# Pinscape_Pico_Expansion_Board_-_DIY_Frie.net
KiCad netlist of a schematic drawn in EAGLE
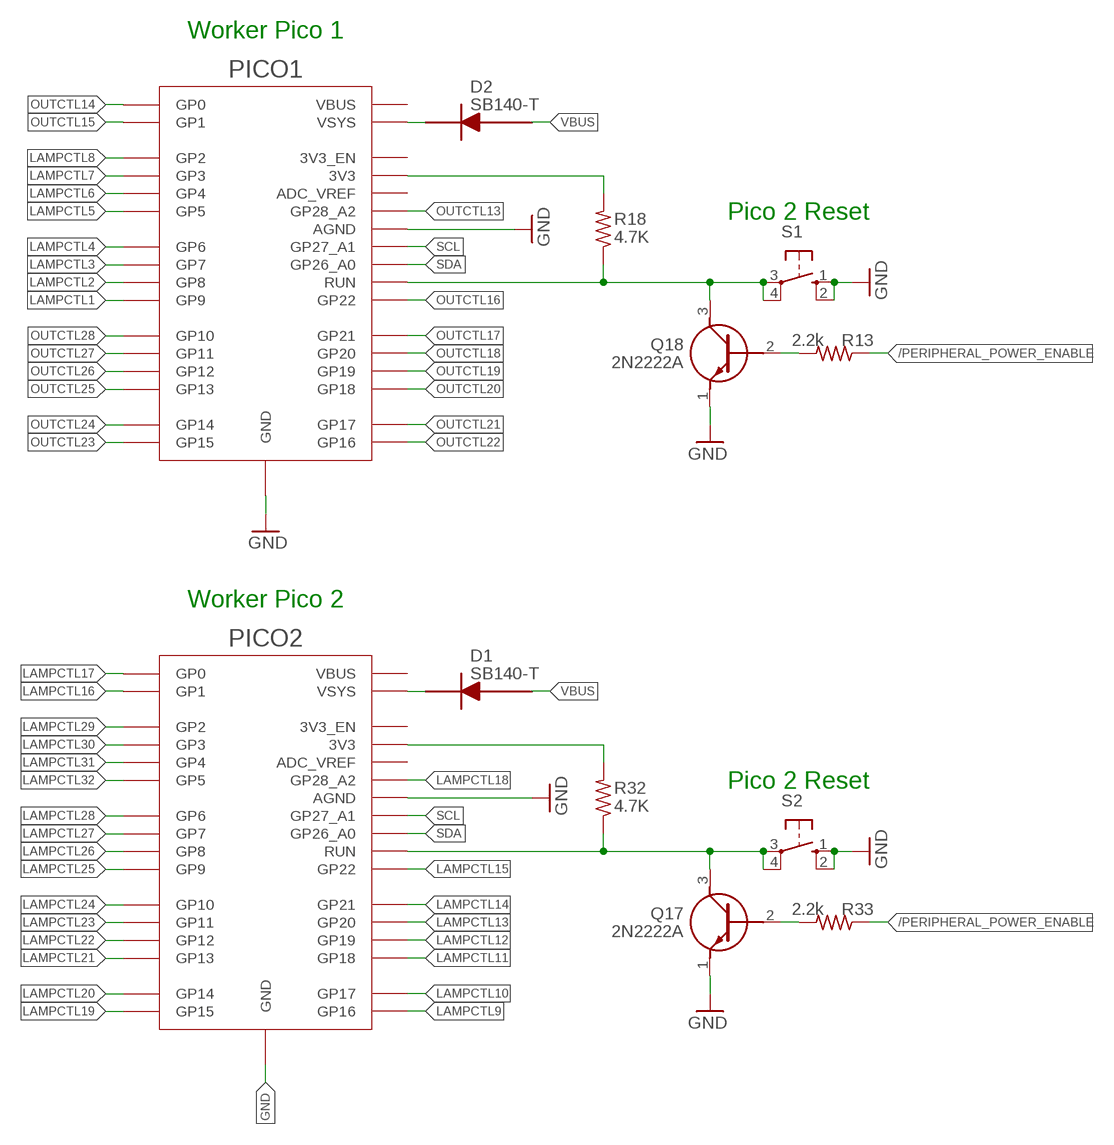
[diagram p0: schematic, sheet 1]
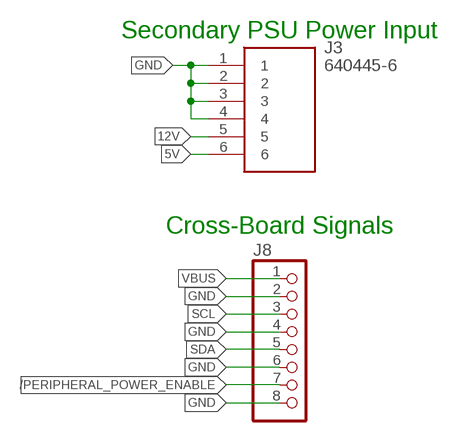
[diagram p1: schematic, sheet 2]
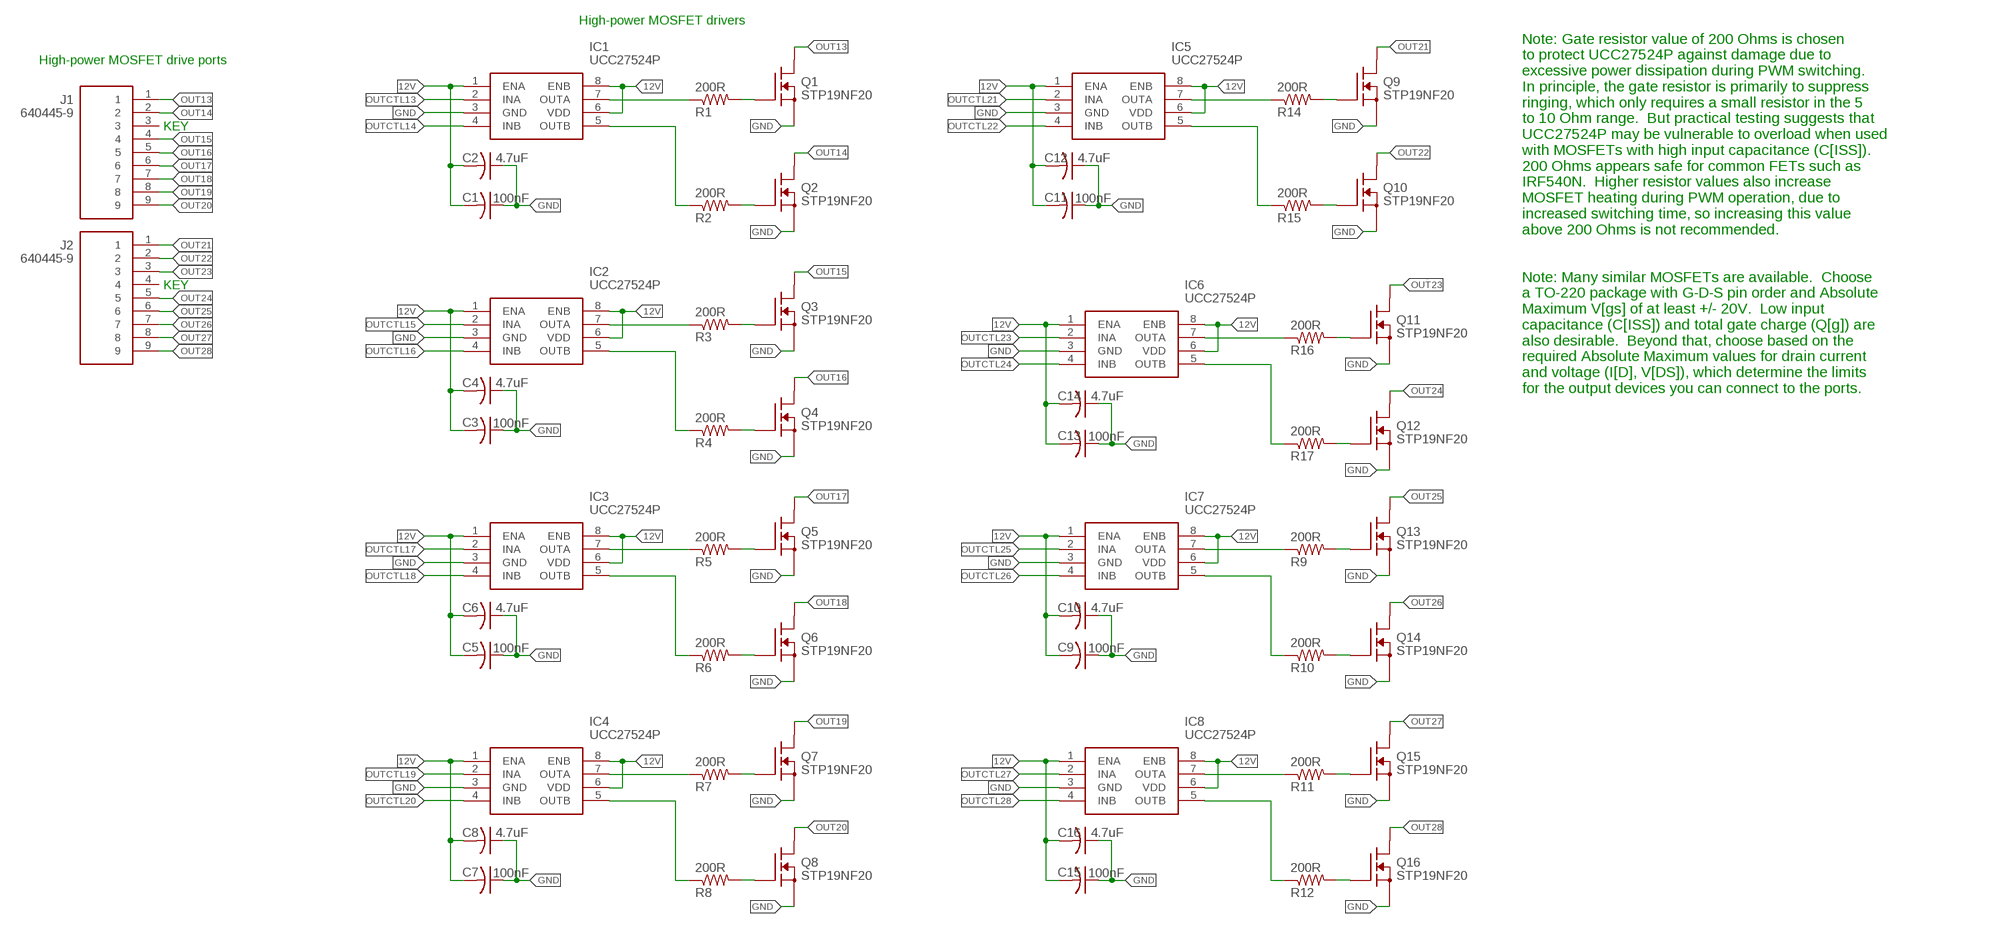
[diagram p2: schematic, sheet 3]
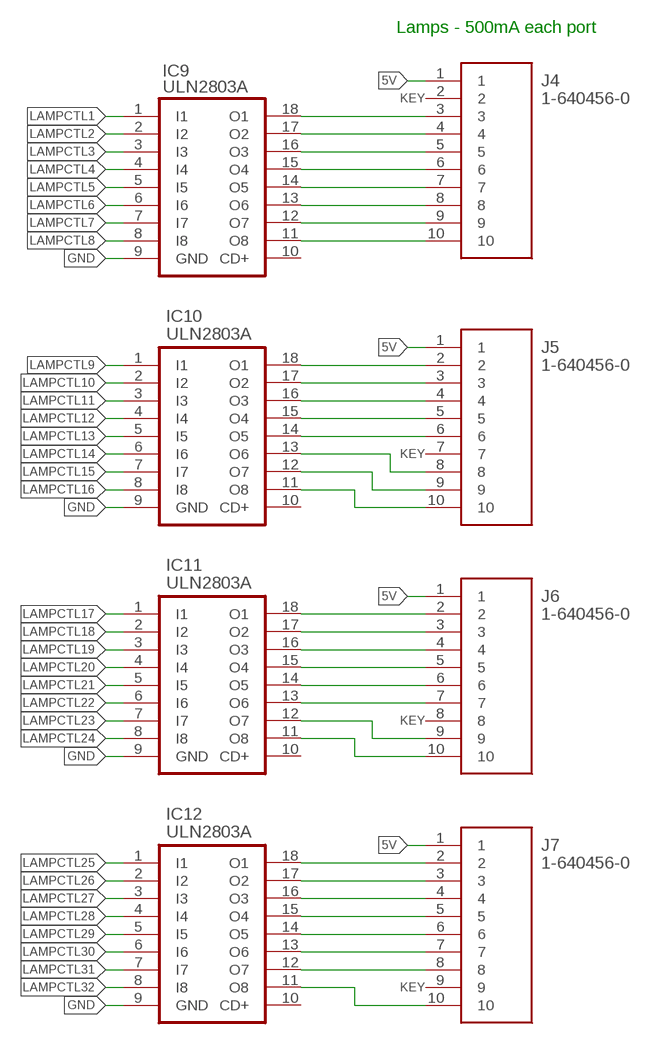
[diagram p3: schematic, sheet 4]
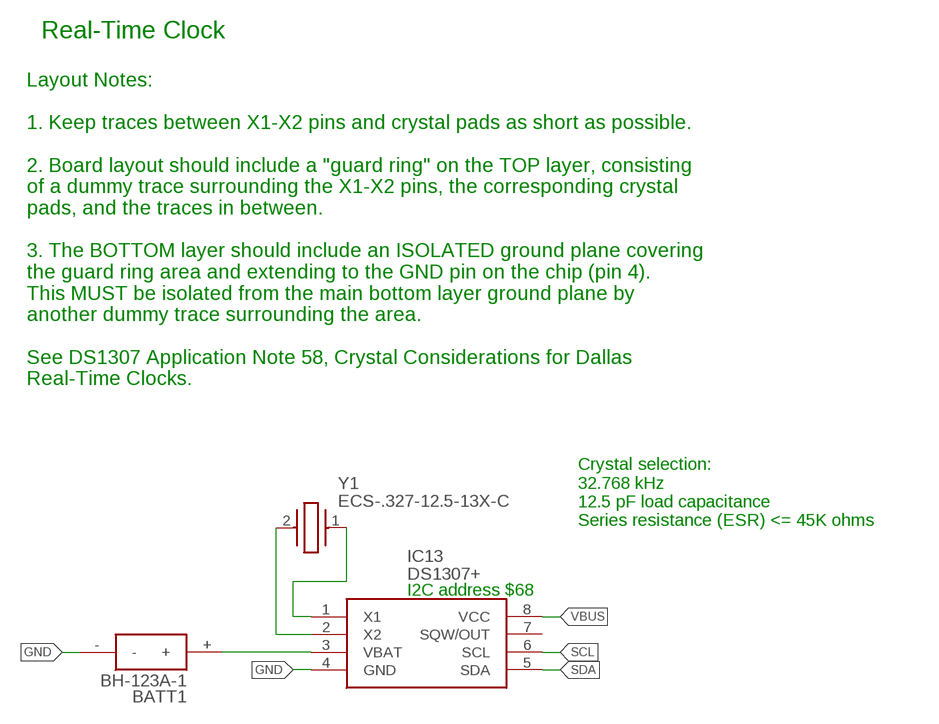
[diagram p4: schematic, sheet 5]
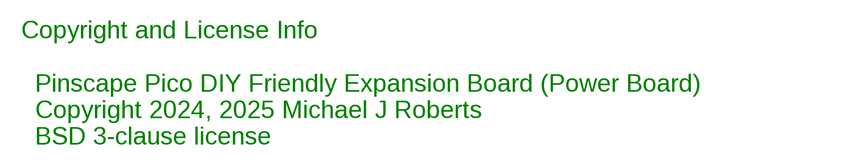
[diagram p5: schematic, sheet 6]

(export (version "E")
  (design (tool "Eeschema 10.0.6"))
  (components
    (comp (ref "C1")
      (value "100nF")
      (footprint "eagle-import:C025-024X044")
      (fields (field (name "PARTNO") "21RZ310-RC"))
      (libsource (lib "eagle-import") (part "C-US025-024X044"))
    )
    (comp (ref "C2")
      (value "4.7uF")
      (footprint "eagle-import:C025-024X044")
      (fields (field (name "PARTNO") "810-FG14X5R1H475KRT0"))
      (libsource (lib "eagle-import") (part "C-US025-024X044"))
    )
    (comp (ref "C3")
      (value "100nF")
      (footprint "eagle-import:C025-024X044")
      (fields (field (name "PARTNO") "21RZ310-RC"))
      (libsource (lib "eagle-import") (part "C-US025-024X044"))
    )
    (comp (ref "C4")
      (value "4.7uF")
      (footprint "eagle-import:C025-024X044")
      (fields (field (name "PARTNO") "810-FG14X5R1H475KRT0"))
      (libsource (lib "eagle-import") (part "C-US025-024X044"))
    )
    (comp (ref "C5")
      (value "100nF")
      (footprint "eagle-import:C025-024X044")
      (fields (field (name "PARTNO") "21RZ310-RC"))
      (libsource (lib "eagle-import") (part "C-US025-024X044"))
    )
    (comp (ref "C6")
      (value "4.7uF")
      (footprint "eagle-import:C025-024X044")
      (fields (field (name "PARTNO") "810-FG14X5R1H475KRT0"))
      (libsource (lib "eagle-import") (part "C-US025-024X044"))
    )
    (comp (ref "C7")
      (value "100nF")
      (footprint "eagle-import:C025-024X044")
      (fields (field (name "PARTNO") "21RZ310-RC"))
      (libsource (lib "eagle-import") (part "C-US025-024X044"))
    )
    (comp (ref "C8")
      (value "4.7uF")
      (footprint "eagle-import:C025-024X044")
      (fields (field (name "PARTNO") "810-FG14X5R1H475KRT0"))
      (libsource (lib "eagle-import") (part "C-US025-024X044"))
    )
    (comp (ref "C9")
      (value "100nF")
      (footprint "eagle-import:C025-024X044")
      (fields (field (name "PARTNO") "21RZ310-RC"))
      (libsource (lib "eagle-import") (part "C-US025-024X044"))
    )
    (comp (ref "C10")
      (value "4.7uF")
      (footprint "eagle-import:C025-024X044")
      (fields (field (name "PARTNO") "810-FG14X5R1H475KRT0"))
      (libsource (lib "eagle-import") (part "C-US025-024X044"))
    )
    (comp (ref "C11")
      (value "100nF")
      (footprint "eagle-import:C025-024X044")
      (fields (field (name "PARTNO") "21RZ310-RC"))
      (libsource (lib "eagle-import") (part "C-US025-024X044"))
    )
    (comp (ref "C12")
      (value "4.7uF")
      (footprint "eagle-import:C025-024X044")
      (fields (field (name "PARTNO") "810-FG14X5R1H475KRT0"))
      (libsource (lib "eagle-import") (part "C-US025-024X044"))
    )
    (comp (ref "C13")
      (value "100nF")
      (footprint "eagle-import:C025-024X044")
      (fields (field (name "PARTNO") "21RZ310-RC"))
      (libsource (lib "eagle-import") (part "C-US025-024X044"))
    )
    (comp (ref "C14")
      (value "4.7uF")
      (footprint "eagle-import:C025-024X044")
      (fields (field (name "PARTNO") "810-FG14X5R1H475KRT0"))
      (libsource (lib "eagle-import") (part "C-US025-024X044"))
    )
    (comp (ref "C15")
      (value "100nF")
      (footprint "eagle-import:C025-024X044")
      (fields (field (name "PARTNO") "21RZ310-RC"))
      (libsource (lib "eagle-import") (part "C-US025-024X044"))
    )
    (comp (ref "C16")
      (value "4.7uF")
      (footprint "eagle-import:C025-024X044")
      (fields (field (name "PARTNO") "810-FG14X5R1H475KRT0"))
      (libsource (lib "eagle-import") (part "C-US025-024X044"))
    )
    (comp (ref "IC1")
      (value "UCC27524P")
      (footprint "eagle-import:DIP794W53P254L959H508Q8N")
      (fields (field (name "MOUSER_PART_NUMBER") "595-UCC27524P"))
      (libsource (lib "eagle-import") (part "UCC27524P"))
    )
    (comp (ref "IC2")
      (value "UCC27524P")
      (footprint "eagle-import:DIP794W53P254L959H508Q8N")
      (fields (field (name "MOUSER_PART_NUMBER") "595-UCC27524P"))
      (libsource (lib "eagle-import") (part "UCC27524P"))
    )
    (comp (ref "IC3")
      (value "UCC27524P")
      (footprint "eagle-import:DIP794W53P254L959H508Q8N")
      (fields (field (name "MOUSER_PART_NUMBER") "595-UCC27524P"))
      (libsource (lib "eagle-import") (part "UCC27524P"))
    )
    (comp (ref "IC4")
      (value "UCC27524P")
      (footprint "eagle-import:DIP794W53P254L959H508Q8N")
      (fields (field (name "MOUSER_PART_NUMBER") "595-UCC27524P"))
      (libsource (lib "eagle-import") (part "UCC27524P"))
    )
    (comp (ref "IC5")
      (value "UCC27524P")
      (footprint "eagle-import:DIP794W53P254L959H508Q8N")
      (fields (field (name "MOUSER_PART_NUMBER") "595-UCC27524P"))
      (libsource (lib "eagle-import") (part "UCC27524P"))
    )
    (comp (ref "IC6")
      (value "UCC27524P")
      (footprint "eagle-import:DIP794W53P254L959H508Q8N")
      (fields (field (name "MOUSER_PART_NUMBER") "595-UCC27524P"))
      (libsource (lib "eagle-import") (part "UCC27524P"))
    )
    (comp (ref "IC7")
      (value "UCC27524P")
      (footprint "eagle-import:DIP794W53P254L959H508Q8N")
      (fields (field (name "MOUSER_PART_NUMBER") "595-UCC27524P"))
      (libsource (lib "eagle-import") (part "UCC27524P"))
    )
    (comp (ref "IC8")
      (value "UCC27524P")
      (footprint "eagle-import:DIP794W53P254L959H508Q8N")
      (fields (field (name "MOUSER_PART_NUMBER") "595-UCC27524P"))
      (libsource (lib "eagle-import") (part "UCC27524P"))
    )
    (comp (ref "J1")
      (value "640445-9")
      (footprint "eagle-import:SHDR9W117P0X396_1X9_3566X762X1")
      (fields (field (name "MOUSER_PART_NUMBER") "571-6404459"))
      (libsource (lib "eagle-import") (part "640445-9"))
    )
    (comp (ref "J2")
      (value "640445-9")
      (footprint "eagle-import:SHDR9W117P0X396_1X9_3566X762X1")
      (fields (field (name "MOUSER_PART_NUMBER") "571-6404459"))
      (libsource (lib "eagle-import") (part "640445-9"))
    )
    (comp (ref "Q1")
      (value "STP19NF20")
      (footprint "eagle-import:TO220BV")
      (fields (field (name "PARTNO") "FDPF085N10A"))
      (libsource (lib "eagle-import") (part "BUK7575-55A"))
    )
    (comp (ref "Q2")
      (value "STP19NF20")
      (footprint "eagle-import:TO220BV")
      (fields (field (name "PARTNO") "FDPF085N10A"))
      (libsource (lib "eagle-import") (part "BUK7575-55A"))
    )
    (comp (ref "Q3")
      (value "STP19NF20")
      (footprint "eagle-import:TO220BV")
      (fields (field (name "PARTNO") "FDPF085N10A"))
      (libsource (lib "eagle-import") (part "BUK7575-55A"))
    )
    (comp (ref "Q4")
      (value "STP19NF20")
      (footprint "eagle-import:TO220BV")
      (fields (field (name "PARTNO") "FDPF085N10A"))
      (libsource (lib "eagle-import") (part "BUK7575-55A"))
    )
    (comp (ref "Q5")
      (value "STP19NF20")
      (footprint "eagle-import:TO220BV")
      (fields (field (name "PARTNO") "FDPF085N10A"))
      (libsource (lib "eagle-import") (part "BUK7575-55A"))
    )
    (comp (ref "Q6")
      (value "STP19NF20")
      (footprint "eagle-import:TO220BV")
      (fields (field (name "PARTNO") "FDPF085N10A"))
      (libsource (lib "eagle-import") (part "BUK7575-55A"))
    )
    (comp (ref "Q7")
      (value "STP19NF20")
      (footprint "eagle-import:TO220BV")
      (fields (field (name "PARTNO") "FDPF085N10A"))
      (libsource (lib "eagle-import") (part "BUK7575-55A"))
    )
    (comp (ref "Q8")
      (value "STP19NF20")
      (footprint "eagle-import:TO220BV")
      (fields (field (name "PARTNO") "FDPF085N10A"))
      (libsource (lib "eagle-import") (part "BUK7575-55A"))
    )
    (comp (ref "Q9")
      (value "STP19NF20")
      (footprint "eagle-import:TO220BV")
      (fields (field (name "PARTNO") "FDPF085N10A"))
      (libsource (lib "eagle-import") (part "BUK7575-55A"))
    )
    (comp (ref "Q10")
      (value "STP19NF20")
      (footprint "eagle-import:TO220BV")
      (fields (field (name "PARTNO") "FDPF085N10A"))
      (libsource (lib "eagle-import") (part "BUK7575-55A"))
    )
    (comp (ref "Q11")
      (value "STP19NF20")
      (footprint "eagle-import:TO220BV")
      (fields (field (name "PARTNO") "FDPF085N10A"))
      (libsource (lib "eagle-import") (part "BUK7575-55A"))
    )
    (comp (ref "Q12")
      (value "STP19NF20")
      (footprint "eagle-import:TO220BV")
      (fields (field (name "PARTNO") "FDPF085N10A"))
      (libsource (lib "eagle-import") (part "BUK7575-55A"))
    )
    (comp (ref "Q13")
      (value "STP19NF20")
      (footprint "eagle-import:TO220BV")
      (fields (field (name "PARTNO") "FDPF085N10A"))
      (libsource (lib "eagle-import") (part "BUK7575-55A"))
    )
    (comp (ref "Q14")
      (value "STP19NF20")
      (footprint "eagle-import:TO220BV")
      (fields (field (name "PARTNO") "FDPF085N10A"))
      (libsource (lib "eagle-import") (part "BUK7575-55A"))
    )
    (comp (ref "Q15")
      (value "STP19NF20")
      (footprint "eagle-import:TO220BV")
      (fields (field (name "PARTNO") "FDPF085N10A"))
      (libsource (lib "eagle-import") (part "BUK7575-55A"))
    )
    (comp (ref "Q16")
      (value "STP19NF20")
      (footprint "eagle-import:TO220BV")
      (fields (field (name "PARTNO") "FDPF085N10A"))
      (libsource (lib "eagle-import") (part "BUK7575-55A"))
    )
    (comp (ref "R1")
      (value "200R")
      (footprint "eagle-import:0204_5")
      (fields (field (name "PARTNO") "660-MFS1/4DCT52R47R0"))
      (libsource (lib "eagle-import") (part "R-US_0204/5"))
    )
    (comp (ref "R2")
      (value "200R")
      (footprint "eagle-import:0204_5")
      (fields (field (name "PARTNO") "660-MFS1/4DCT52R47R0"))
      (libsource (lib "eagle-import") (part "R-US_0204/5"))
    )
    (comp (ref "R3")
      (value "200R")
      (footprint "eagle-import:0204_5")
      (fields (field (name "PARTNO") "660-MFS1/4DCT52R47R0"))
      (libsource (lib "eagle-import") (part "R-US_0204/5"))
    )
    (comp (ref "R4")
      (value "200R")
      (footprint "eagle-import:0204_5")
      (fields (field (name "PARTNO") "660-MFS1/4DCT52R47R0"))
      (libsource (lib "eagle-import") (part "R-US_0204/5"))
    )
    (comp (ref "R5")
      (value "200R")
      (footprint "eagle-import:0204_5")
      (fields (field (name "PARTNO") "660-MFS1/4DCT52R47R0"))
      (libsource (lib "eagle-import") (part "R-US_0204/5"))
    )
    (comp (ref "R6")
      (value "200R")
      (footprint "eagle-import:0204_5")
      (fields (field (name "PARTNO") "660-MFS1/4DCT52R47R0"))
      (libsource (lib "eagle-import") (part "R-US_0204/5"))
    )
    (comp (ref "R7")
      (value "200R")
      (footprint "eagle-import:0204_5")
      (fields (field (name "PARTNO") "660-MFS1/4DCT52R47R0"))
      (libsource (lib "eagle-import") (part "R-US_0204/5"))
    )
    (comp (ref "R8")
      (value "200R")
      (footprint "eagle-import:0204_5")
      (fields (field (name "PARTNO") "660-MFS1/4DCT52R47R0"))
      (libsource (lib "eagle-import") (part "R-US_0204/5"))
    )
    (comp (ref "R9")
      (value "200R")
      (footprint "eagle-import:0204_5")
      (fields (field (name "PARTNO") "660-MFS1/4DCT52R47R0"))
      (libsource (lib "eagle-import") (part "R-US_0204/5"))
    )
    (comp (ref "R10")
      (value "200R")
      (footprint "eagle-import:0204_5")
      (fields (field (name "PARTNO") "660-MFS1/4DCT52R47R0"))
      (libsource (lib "eagle-import") (part "R-US_0204/5"))
    )
    (comp (ref "R11")
      (value "200R")
      (footprint "eagle-import:0204_5")
      (fields (field (name "PARTNO") "660-MFS1/4DCT52R47R0"))
      (libsource (lib "eagle-import") (part "R-US_0204/5"))
    )
    (comp (ref "R12")
      (value "200R")
      (footprint "eagle-import:0204_5")
      (fields (field (name "PARTNO") "660-MFS1/4DCT52R47R0"))
      (libsource (lib "eagle-import") (part "R-US_0204/5"))
    )
    (comp (ref "R14")
      (value "200R")
      (footprint "eagle-import:0204_5")
      (fields (field (name "PARTNO") "660-MFS1/4DCT52R47R0"))
      (libsource (lib "eagle-import") (part "R-US_0204/5"))
    )
    (comp (ref "R15")
      (value "200R")
      (footprint "eagle-import:0204_5")
      (fields (field (name "PARTNO") "660-MFS1/4DCT52R47R0"))
      (libsource (lib "eagle-import") (part "R-US_0204/5"))
    )
    (comp (ref "R16")
      (value "200R")
      (footprint "eagle-import:0204_5")
      (fields (field (name "PARTNO") "660-MFS1/4DCT52R47R0"))
      (libsource (lib "eagle-import") (part "R-US_0204/5"))
    )
    (comp (ref "R17")
      (value "200R")
      (footprint "eagle-import:0204_5")
      (fields (field (name "PARTNO") "660-MFS1/4DCT52R47R0"))
      (libsource (lib "eagle-import") (part "R-US_0204/5"))
    )
    (comp (ref "BATT1")
      (value "BH-123A-1")
      (footprint "eagle-import:BH-123A-1")
      (libsource (lib "eagle-import") (part "BH-123A-1"))
    )
    (comp (ref "IC13")
      (value "DS1307+")
      (footprint "eagle-import:DIP794W56P254L938H457Q8N")
      (fields (field (name "MOUSER_PART_NUMBER") "700-DS1307"))
      (libsource (lib "eagle-import") (part "DS1307+"))
    )
    (comp (ref "Y1")
      (value "ECS-.327-12.5-13X-C")
      (footprint "eagle-import:ECS32712513XC")
      (fields (field (name "MOUSER_PART_NUMBER") "520-S-.32712.513XC"))
      (libsource (lib "eagle-import") (part "ECS-.327-12.5-13X-C"))
    )
    (comp (ref "IC9")
      (value "ULN2803A")
      (footprint "eagle-import:DIL18")
      (libsource (lib "eagle-import") (part "ULN2803A"))
    )
    (comp (ref "IC10")
      (value "ULN2803A")
      (footprint "eagle-import:DIL18")
      (libsource (lib "eagle-import") (part "ULN2803A"))
    )
    (comp (ref "IC11")
      (value "ULN2803A")
      (footprint "eagle-import:DIL18")
      (libsource (lib "eagle-import") (part "ULN2803A"))
    )
    (comp (ref "IC12")
      (value "ULN2803A")
      (footprint "eagle-import:DIL18")
      (libsource (lib "eagle-import") (part "ULN2803A"))
    )
    (comp (ref "J4")
      (value "1-640456-0")
      (footprint "eagle-import:SHDR10W66P0X254_1X10_2540X572X")
      (fields (field (name "MOUSER_PART_NUMBER") "571-16404560"))
      (libsource (lib "eagle-import") (part "1-640456-0"))
    )
    (comp (ref "J5")
      (value "1-640456-0")
      (footprint "eagle-import:SHDR10W66P0X254_1X10_2540X572X")
      (fields (field (name "MOUSER_PART_NUMBER") "571-16404560"))
      (libsource (lib "eagle-import") (part "1-640456-0"))
    )
    (comp (ref "J6")
      (value "1-640456-0")
      (footprint "eagle-import:SHDR10W66P0X254_1X10_2540X572X")
      (fields (field (name "MOUSER_PART_NUMBER") "571-16404560"))
      (libsource (lib "eagle-import") (part "1-640456-0"))
    )
    (comp (ref "J7")
      (value "1-640456-0")
      (footprint "eagle-import:SHDR10W66P0X254_1X10_2540X572X")
      (fields (field (name "MOUSER_PART_NUMBER") "571-16404560"))
      (libsource (lib "eagle-import") (part "1-640456-0"))
    )
    (comp (ref "D1")
      (value "SB140-T")
      (footprint "eagle-import:DIOAD1408W86L464D236")
      (fields (field (name "MOUSER_PART_NUMBER") "621-SB140-T"))
      (libsource (lib "eagle-import") (part "SB140-T"))
    )
    (comp (ref "D2")
      (value "SB140-T")
      (footprint "eagle-import:DIOAD1408W86L464D236")
      (fields (field (name "MOUSER_PART_NUMBER") "621-SB140-T"))
      (libsource (lib "eagle-import") (part "SB140-T"))
    )
    (comp (ref "PICO1")
      (value "RPI_PICO_NO_DEBUG")
      (footprint "eagle-import:RPI_PICO_TH_NO_DEBUG")
      (libsource (lib "eagle-import") (part "RPI_PICO_NO_DEBUG"))
    )
    (comp (ref "PICO2")
      (value "RPI_PICO_NO_DEBUG")
      (footprint "eagle-import:RPI_PICO_TH_NO_DEBUG")
      (libsource (lib "eagle-import") (part "RPI_PICO_NO_DEBUG"))
    )
    (comp (ref "Q17")
      (value "2N2222A")
      (footprint "eagle-import:2N2222A")
      (fields (field (name "MOUSER_PART_NUMBER") "637-2N2222A"))
      (libsource (lib "eagle-import") (part "2N2222A"))
    )
    (comp (ref "Q18")
      (value "2N2222A")
      (footprint "eagle-import:2N2222A")
      (fields (field (name "MOUSER_PART_NUMBER") "637-2N2222A"))
      (libsource (lib "eagle-import") (part "2N2222A"))
    )
    (comp (ref "R13")
      (value "2.2k")
      (footprint "eagle-import:0204_7")
      (fields (field (name "PARTNO") "660-MFS1/4DCT52R47R0"))
      (libsource (lib "eagle-import") (part "R-US_0204/7"))
    )
    (comp (ref "R18")
      (value "4.7K")
      (footprint "eagle-import:0204_7")
      (fields (field (name "PARTNO") "660-MFS1/4DCT52R47R0"))
      (libsource (lib "eagle-import") (part "R-US_0204/7"))
    )
    (comp (ref "R32")
      (value "4.7K")
      (footprint "eagle-import:0204_7")
      (fields (field (name "PARTNO") "660-MFS1/4DCT52R47R0"))
      (libsource (lib "eagle-import") (part "R-US_0204/7"))
    )
    (comp (ref "R33")
      (value "2.2k")
      (footprint "eagle-import:0204_7")
      (fields (field (name "PARTNO") "660-MFS1/4DCT52R47R0"))
      (libsource (lib "eagle-import") (part "R-US_0204/7"))
    )
    (comp (ref "S1")
      (value "10-XX")
      (footprint "eagle-import:B3F-10XX")
      (fields (field (name "MPN") "B3F-1000"))
      (libsource (lib "eagle-import") (part "10-XX"))
    )
    (comp (ref "S2")
      (value "10-XX")
      (footprint "eagle-import:B3F-10XX")
      (fields (field (name "MPN") "B3F-1000"))
      (libsource (lib "eagle-import") (part "10-XX"))
    )
    (comp (ref "J3")
      (value "640445-6")
      (footprint "eagle-import:SHDR6W183P0X396_1X6_2377X762X1")
      (fields (field (name "MOUSER_PART_NUMBER") "571-6404456"))
      (libsource (lib "eagle-import") (part "640445-6"))
    )
    (comp (ref "J8")
      (value "PINHD-1X8/90")
      (footprint "eagle-import:1X08_90")
      (libsource (lib "eagle-import") (part "PINHD-1X8/90"))
    )
  )
  (nets
    (net (code "1") (name "5V") (class "Default")
      (node (ref "J3") (pin "6") (pinfunction "6_6") (pintype "bidirectional"))
      (node (ref "J4") (pin "1") (pinfunction "1_1") (pintype "bidirectional"))
      (node (ref "J5") (pin "1") (pinfunction "1_1") (pintype "bidirectional"))
      (node (ref "J6") (pin "1") (pinfunction "1_1") (pintype "bidirectional"))
      (node (ref "J7") (pin "1") (pinfunction "1_1") (pintype "bidirectional"))
    )
    (net (code "2") (name "12V") (class "Default")
      (node (ref "C1") (pin "2") (pinfunction "2_2") (pintype "passive"))
      (node (ref "C10") (pin "2") (pinfunction "2_2") (pintype "passive"))
      (node (ref "C11") (pin "2") (pinfunction "2_2") (pintype "passive"))
      (node (ref "C12") (pin "2") (pinfunction "2_2") (pintype "passive"))
      (node (ref "C13") (pin "2") (pinfunction "2_2") (pintype "passive"))
      (node (ref "C14") (pin "2") (pinfunction "2_2") (pintype "passive"))
      (node (ref "C15") (pin "2") (pinfunction "2_2") (pintype "passive"))
      (node (ref "C16") (pin "2") (pinfunction "2_2") (pintype "passive"))
      (node (ref "C2") (pin "2") (pinfunction "2_2") (pintype "passive"))
      (node (ref "C3") (pin "2") (pinfunction "2_2") (pintype "passive"))
      (node (ref "C4") (pin "2") (pinfunction "2_2") (pintype "passive"))
      (node (ref "C5") (pin "2") (pinfunction "2_2") (pintype "passive"))
      (node (ref "C6") (pin "2") (pinfunction "2_2") (pintype "passive"))
      (node (ref "C7") (pin "2") (pinfunction "2_2") (pintype "passive"))
      (node (ref "C8") (pin "2") (pinfunction "2_2") (pintype "passive"))
      (node (ref "C9") (pin "2") (pinfunction "2_2") (pintype "passive"))
      (node (ref "IC1") (pin "1") (pinfunction "ENA_1") (pintype "input"))
      (node (ref "IC1") (pin "6") (pinfunction "VDD_6") (pintype "power_in"))
      (node (ref "IC1") (pin "8") (pinfunction "ENB_8") (pintype "input"))
      (node (ref "IC2") (pin "1") (pinfunction "ENA_1") (pintype "input"))
      (node (ref "IC2") (pin "6") (pinfunction "VDD_6") (pintype "power_in"))
      (node (ref "IC2") (pin "8") (pinfunction "ENB_8") (pintype "input"))
      (node (ref "IC3") (pin "1") (pinfunction "ENA_1") (pintype "input"))
      (node (ref "IC3") (pin "6") (pinfunction "VDD_6") (pintype "power_in"))
      (node (ref "IC3") (pin "8") (pinfunction "ENB_8") (pintype "input"))
      (node (ref "IC4") (pin "1") (pinfunction "ENA_1") (pintype "input"))
      (node (ref "IC4") (pin "6") (pinfunction "VDD_6") (pintype "power_in"))
      (node (ref "IC4") (pin "8") (pinfunction "ENB_8") (pintype "input"))
      (node (ref "IC5") (pin "1") (pinfunction "ENA_1") (pintype "input"))
      (node (ref "IC5") (pin "6") (pinfunction "VDD_6") (pintype "power_in"))
      (node (ref "IC5") (pin "8") (pinfunction "ENB_8") (pintype "input"))
      (node (ref "IC6") (pin "1") (pinfunction "ENA_1") (pintype "input"))
      (node (ref "IC6") (pin "6") (pinfunction "VDD_6") (pintype "power_in"))
      (node (ref "IC6") (pin "8") (pinfunction "ENB_8") (pintype "input"))
      (node (ref "IC7") (pin "1") (pinfunction "ENA_1") (pintype "input"))
      (node (ref "IC7") (pin "6") (pinfunction "VDD_6") (pintype "power_in"))
      (node (ref "IC7") (pin "8") (pinfunction "ENB_8") (pintype "input"))
      (node (ref "IC8") (pin "1") (pinfunction "ENA_1") (pintype "input"))
      (node (ref "IC8") (pin "6") (pinfunction "VDD_6") (pintype "power_in"))
      (node (ref "IC8") (pin "8") (pinfunction "ENB_8") (pintype "input"))
      (node (ref "J3") (pin "5") (pinfunction "5_5") (pintype "bidirectional"))
    )
    (net (code "3") (name "GND") (class "Default")
      (node (ref "BATT1") (pin "-") (pinfunction "-_-") (pintype "bidirectional"))
      (node (ref "C1") (pin "1") (pinfunction "1_1") (pintype "passive"))
      (node (ref "C10") (pin "1") (pinfunction "1_1") (pintype "passive"))
      (node (ref "C11") (pin "1") (pinfunction "1_1") (pintype "passive"))
      (node (ref "C12") (pin "1") (pinfunction "1_1") (pintype "passive"))
      (node (ref "C13") (pin "1") (pinfunction "1_1") (pintype "passive"))
      (node (ref "C14") (pin "1") (pinfunction "1_1") (pintype "passive"))
      (node (ref "C15") (pin "1") (pinfunction "1_1") (pintype "passive"))
      (node (ref "C16") (pin "1") (pinfunction "1_1") (pintype "passive"))
      (node (ref "C2") (pin "1") (pinfunction "1_1") (pintype "passive"))
      (node (ref "C3") (pin "1") (pinfunction "1_1") (pintype "passive"))
      (node (ref "C4") (pin "1") (pinfunction "1_1") (pintype "passive"))
      (node (ref "C5") (pin "1") (pinfunction "1_1") (pintype "passive"))
      (node (ref "C6") (pin "1") (pinfunction "1_1") (pintype "passive"))
      (node (ref "C7") (pin "1") (pinfunction "1_1") (pintype "passive"))
      (node (ref "C8") (pin "1") (pinfunction "1_1") (pintype "passive"))
      (node (ref "C9") (pin "1") (pinfunction "1_1") (pintype "passive"))
      (node (ref "IC1") (pin "3") (pinfunction "GND_3") (pintype "power_in"))
      (node (ref "IC10") (pin "9") (pinfunction "GND_9") (pintype "power_in"))
      (node (ref "IC11") (pin "9") (pinfunction "GND_9") (pintype "power_in"))
      (node (ref "IC12") (pin "9") (pinfunction "GND_9") (pintype "power_in"))
      (node (ref "IC13") (pin "4") (pinfunction "GND_4") (pintype "bidirectional"))
      (node (ref "IC2") (pin "3") (pinfunction "GND_3") (pintype "power_in"))
      (node (ref "IC3") (pin "3") (pinfunction "GND_3") (pintype "power_in"))
      (node (ref "IC4") (pin "3") (pinfunction "GND_3") (pintype "power_in"))
      (node (ref "IC5") (pin "3") (pinfunction "GND_3") (pintype "power_in"))
      (node (ref "IC6") (pin "3") (pinfunction "GND_3") (pintype "power_in"))
      (node (ref "IC7") (pin "3") (pinfunction "GND_3") (pintype "power_in"))
      (node (ref "IC8") (pin "3") (pinfunction "GND_3") (pintype "power_in"))
      (node (ref "IC9") (pin "9") (pinfunction "GND_9") (pintype "power_in"))
      (node (ref "J3") (pin "1") (pinfunction "1_1") (pintype "bidirectional"))
      (node (ref "J3") (pin "2") (pinfunction "2_2") (pintype "bidirectional"))
      (node (ref "J3") (pin "3") (pinfunction "3_3") (pintype "bidirectional"))
      (node (ref "J3") (pin "4") (pinfunction "4_4") (pintype "bidirectional"))
      (node (ref "J8") (pin "2") (pinfunction "2_2") (pintype "passive"))
      (node (ref "J8") (pin "4") (pinfunction "4_4") (pintype "passive"))
      (node (ref "J8") (pin "6") (pinfunction "6_6") (pintype "passive"))
      (node (ref "J8") (pin "8") (pinfunction "8_8") (pintype "passive"))
      (node (ref "PICO1") (pin "AGND") (pinfunction "AGND_AGND") (pintype "bidirectional"))
      (node (ref "PICO1") (pin "GND@1") (pinfunction "GND_GND@1") (pintype "bidirectional"))
      (node (ref "PICO1") (pin "GND@2") (pinfunction "GND_GND@2") (pintype "bidirectional"))
      (node (ref "PICO1") (pin "GND@3") (pinfunction "GND_GND@3") (pintype "bidirectional"))
      (node (ref "PICO1") (pin "GND@4") (pinfunction "GND_GND@4") (pintype "bidirectional"))
      (node (ref "PICO1") (pin "GND@6") (pinfunction "GND_GND@6") (pintype "bidirectional"))
      (node (ref "PICO1") (pin "GND@7") (pinfunction "GND_GND@7") (pintype "bidirectional"))
      (node (ref "PICO1") (pin "GND@8") (pinfunction "GND_GND@8") (pintype "bidirectional"))
      (node (ref "PICO2") (pin "AGND") (pinfunction "AGND_AGND") (pintype "bidirectional"))
      (node (ref "PICO2") (pin "GND@1") (pinfunction "GND_GND@1") (pintype "bidirectional"))
      (node (ref "PICO2") (pin "GND@2") (pinfunction "GND_GND@2") (pintype "bidirectional"))
      (node (ref "PICO2") (pin "GND@3") (pinfunction "GND_GND@3") (pintype "bidirectional"))
      (node (ref "PICO2") (pin "GND@4") (pinfunction "GND_GND@4") (pintype "bidirectional"))
      (node (ref "PICO2") (pin "GND@6") (pinfunction "GND_GND@6") (pintype "bidirectional"))
      (node (ref "PICO2") (pin "GND@7") (pinfunction "GND_GND@7") (pintype "bidirectional"))
      (node (ref "PICO2") (pin "GND@8") (pinfunction "GND_GND@8") (pintype "bidirectional"))
      (node (ref "Q1") (pin "3") (pinfunction "S_3") (pintype "passive"))
      (node (ref "Q10") (pin "3") (pinfunction "S_3") (pintype "passive"))
      (node (ref "Q11") (pin "3") (pinfunction "S_3") (pintype "passive"))
      (node (ref "Q12") (pin "3") (pinfunction "S_3") (pintype "passive"))
      (node (ref "Q13") (pin "3") (pinfunction "S_3") (pintype "passive"))
      (node (ref "Q14") (pin "3") (pinfunction "S_3") (pintype "passive"))
      (node (ref "Q15") (pin "3") (pinfunction "S_3") (pintype "passive"))
      (node (ref "Q16") (pin "3") (pinfunction "S_3") (pintype "passive"))
      (node (ref "Q17") (pin "1") (pinfunction "E_1") (pintype "bidirectional"))
      (node (ref "Q18") (pin "1") (pinfunction "E_1") (pintype "bidirectional"))
      (node (ref "Q2") (pin "3") (pinfunction "S_3") (pintype "passive"))
      (node (ref "Q3") (pin "3") (pinfunction "S_3") (pintype "passive"))
      (node (ref "Q4") (pin "3") (pinfunction "S_3") (pintype "passive"))
      (node (ref "Q5") (pin "3") (pinfunction "S_3") (pintype "passive"))
      (node (ref "Q6") (pin "3") (pinfunction "S_3") (pintype "passive"))
      (node (ref "Q7") (pin "3") (pinfunction "S_3") (pintype "passive"))
      (node (ref "Q8") (pin "3") (pinfunction "S_3") (pintype "passive"))
      (node (ref "Q9") (pin "3") (pinfunction "S_3") (pintype "passive"))
      (node (ref "S1") (pin "1") (pinfunction "S_1") (pintype "passive"))
      (node (ref "S1") (pin "2") (pinfunction "S1_2") (pintype "passive"))
      (node (ref "S2") (pin "1") (pinfunction "S_1") (pintype "passive"))
      (node (ref "S2") (pin "2") (pinfunction "S1_2") (pintype "passive"))
    )
    (net (code "4") (name "LAMPCTL1") (class "Default")
      (node (ref "IC9") (pin "1") (pinfunction "I1_1") (pintype "input"))
      (node (ref "PICO1") (pin "GP9") (pinfunction "GP9_GP9") (pintype "bidirectional"))
    )
    (net (code "5") (name "LAMPCTL2") (class "Default")
      (node (ref "IC9") (pin "2") (pinfunction "I2_2") (pintype "input"))
      (node (ref "PICO1") (pin "GP8") (pinfunction "GP8_GP8") (pintype "bidirectional"))
    )
    (net (code "6") (name "LAMPCTL3") (class "Default")
      (node (ref "IC9") (pin "3") (pinfunction "I3_3") (pintype "input"))
      (node (ref "PICO1") (pin "GP7") (pinfunction "GP7_GP7") (pintype "bidirectional"))
    )
    (net (code "7") (name "LAMPCTL4") (class "Default")
      (node (ref "IC9") (pin "4") (pinfunction "I4_4") (pintype "input"))
      (node (ref "PICO1") (pin "GP6") (pinfunction "GP6_GP6") (pintype "bidirectional"))
    )
    (net (code "8") (name "LAMPCTL5") (class "Default")
      (node (ref "IC9") (pin "5") (pinfunction "I5_5") (pintype "input"))
      (node (ref "PICO1") (pin "GP5") (pinfunction "GP5_GP5") (pintype "bidirectional"))
    )
    (net (code "9") (name "LAMPCTL6") (class "Default")
      (node (ref "IC9") (pin "6") (pinfunction "I6_6") (pintype "input"))
      (node (ref "PICO1") (pin "GP4") (pinfunction "GP4_GP4") (pintype "bidirectional"))
    )
    (net (code "10") (name "LAMPCTL7") (class "Default")
      (node (ref "IC9") (pin "7") (pinfunction "I7_7") (pintype "input"))
      (node (ref "PICO1") (pin "GP3") (pinfunction "GP3_GP3") (pintype "bidirectional"))
    )
    (net (code "11") (name "LAMPCTL8") (class "Default")
      (node (ref "IC9") (pin "8") (pinfunction "I8_8") (pintype "input"))
      (node (ref "PICO1") (pin "GP2") (pinfunction "GP2_GP2") (pintype "bidirectional"))
    )
    (net (code "12") (name "LAMPCTL9") (class "Default")
      (node (ref "IC10") (pin "1") (pinfunction "I1_1") (pintype "input"))
      (node (ref "PICO2") (pin "GP16") (pinfunction "GP16_GP16") (pintype "bidirectional"))
    )
    (net (code "13") (name "LAMPCTL10") (class "Default")
      (node (ref "IC10") (pin "2") (pinfunction "I2_2") (pintype "input"))
      (node (ref "PICO2") (pin "GP17") (pinfunction "GP17_GP17") (pintype "bidirectional"))
    )
    (net (code "14") (name "LAMPCTL11") (class "Default")
      (node (ref "IC10") (pin "3") (pinfunction "I3_3") (pintype "input"))
      (node (ref "PICO2") (pin "GP18") (pinfunction "GP18_GP18") (pintype "bidirectional"))
    )
    (net (code "15") (name "LAMPCTL12") (class "Default")
      (node (ref "IC10") (pin "4") (pinfunction "I4_4") (pintype "input"))
      (node (ref "PICO2") (pin "GP19") (pinfunction "GP19_GP19") (pintype "bidirectional"))
    )
    (net (code "16") (name "LAMPCTL13") (class "Default")
      (node (ref "IC10") (pin "5") (pinfunction "I5_5") (pintype "input"))
      (node (ref "PICO2") (pin "GP20") (pinfunction "GP20_GP20") (pintype "bidirectional"))
    )
    (net (code "17") (name "LAMPCTL14") (class "Default")
      (node (ref "IC10") (pin "6") (pinfunction "I6_6") (pintype "input"))
      (node (ref "PICO2") (pin "GP21") (pinfunction "GP21_GP21") (pintype "bidirectional"))
    )
    (net (code "18") (name "LAMPCTL15") (class "Default")
      (node (ref "IC10") (pin "7") (pinfunction "I7_7") (pintype "input"))
      (node (ref "PICO2") (pin "GP22") (pinfunction "GP22_GP22") (pintype "bidirectional"))
    )
    (net (code "19") (name "LAMPCTL16") (class "Default")
      (node (ref "IC10") (pin "8") (pinfunction "I8_8") (pintype "input"))
      (node (ref "PICO2") (pin "GP1") (pinfunction "GP1_GP1") (pintype "bidirectional"))
    )
    (net (code "20") (name "LAMPCTL17") (class "Default")
      (node (ref "IC11") (pin "1") (pinfunction "I1_1") (pintype "input"))
      (node (ref "PICO2") (pin "GP0") (pinfunction "GP0_GP0") (pintype "bidirectional"))
    )
    (net (code "21") (name "LAMPCTL18") (class "Default")
      (node (ref "IC11") (pin "2") (pinfunction "I2_2") (pintype "input"))
      (node (ref "PICO2") (pin "GP28_A2") (pinfunction "GP28_A2_GP28_A2") (pintype "bidirectional"))
    )
    (net (code "22") (name "LAMPCTL19") (class "Default")
      (node (ref "IC11") (pin "3") (pinfunction "I3_3") (pintype "input"))
      (node (ref "PICO2") (pin "GP15") (pinfunction "GP15_GP15") (pintype "bidirectional"))
    )
    (net (code "23") (name "LAMPCTL20") (class "Default")
      (node (ref "IC11") (pin "4") (pinfunction "I4_4") (pintype "input"))
      (node (ref "PICO2") (pin "GP14") (pinfunction "GP14_GP14") (pintype "bidirectional"))
    )
    (net (code "24") (name "LAMPCTL21") (class "Default")
      (node (ref "IC11") (pin "5") (pinfunction "I5_5") (pintype "input"))
      (node (ref "PICO2") (pin "GP13") (pinfunction "GP13_GP13") (pintype "bidirectional"))
    )
    (net (code "25") (name "LAMPCTL22") (class "Default")
      (node (ref "IC11") (pin "6") (pinfunction "I6_6") (pintype "input"))
      (node (ref "PICO2") (pin "GP12") (pinfunction "GP12_GP12") (pintype "bidirectional"))
    )
    (net (code "26") (name "LAMPCTL23") (class "Default")
      (node (ref "IC11") (pin "7") (pinfunction "I7_7") (pintype "input"))
      (node (ref "PICO2") (pin "GP11") (pinfunction "GP11_GP11") (pintype "bidirectional"))
    )
    (net (code "27") (name "LAMPCTL24") (class "Default")
      (node (ref "IC11") (pin "8") (pinfunction "I8_8") (pintype "input"))
      (node (ref "PICO2") (pin "GP10") (pinfunction "GP10_GP10") (pintype "bidirectional"))
    )
    (net (code "28") (name "LAMPCTL25") (class "Default")
      (node (ref "IC12") (pin "1") (pinfunction "I1_1") (pintype "input"))
      (node (ref "PICO2") (pin "GP9") (pinfunction "GP9_GP9") (pintype "bidirectional"))
    )
    (net (code "29") (name "LAMPCTL26") (class "Default")
      (node (ref "IC12") (pin "2") (pinfunction "I2_2") (pintype "input"))
      (node (ref "PICO2") (pin "GP8") (pinfunction "GP8_GP8") (pintype "bidirectional"))
    )
    (net (code "30") (name "LAMPCTL27") (class "Default")
      (node (ref "IC12") (pin "3") (pinfunction "I3_3") (pintype "input"))
      (node (ref "PICO2") (pin "GP7") (pinfunction "GP7_GP7") (pintype "bidirectional"))
    )
    (net (code "31") (name "LAMPCTL28") (class "Default")
      (node (ref "IC12") (pin "4") (pinfunction "I4_4") (pintype "input"))
      (node (ref "PICO2") (pin "GP6") (pinfunction "GP6_GP6") (pintype "bidirectional"))
    )
    (net (code "32") (name "LAMPCTL29") (class "Default")
      (node (ref "IC12") (pin "5") (pinfunction "I5_5") (pintype "input"))
      (node (ref "PICO2") (pin "GP2") (pinfunction "GP2_GP2") (pintype "bidirectional"))
    )
    (net (code "33") (name "LAMPCTL30") (class "Default")
      (node (ref "IC12") (pin "6") (pinfunction "I6_6") (pintype "input"))
      (node (ref "PICO2") (pin "GP3") (pinfunction "GP3_GP3") (pintype "bidirectional"))
    )
    (net (code "34") (name "LAMPCTL31") (class "Default")
      (node (ref "IC12") (pin "7") (pinfunction "I7_7") (pintype "input"))
      (node (ref "PICO2") (pin "GP4") (pinfunction "GP4_GP4") (pintype "bidirectional"))
    )
    (net (code "35") (name "LAMPCTL32") (class "Default")
      (node (ref "IC12") (pin "8") (pinfunction "I8_8") (pintype "input"))
      (node (ref "PICO2") (pin "GP5") (pinfunction "GP5_GP5") (pintype "bidirectional"))
    )
    (net (code "36") (name "Net-(D1-K)") (class "Default")
      (node (ref "D1") (pin "1") (pinfunction "K_1") (pintype "bidirectional"))
      (node (ref "PICO2") (pin "VSYS") (pinfunction "VSYS_VSYS") (pintype "bidirectional"))
    )
    (net (code "37") (name "Net-(D2-K)") (class "Default")
      (node (ref "D2") (pin "1") (pinfunction "K_1") (pintype "bidirectional"))
      (node (ref "PICO1") (pin "VSYS") (pinfunction "VSYS_VSYS") (pintype "bidirectional"))
    )
    (net (code "38") (name "Net-(IC1-OUTA)") (class "Default")
      (node (ref "IC1") (pin "7") (pinfunction "OUTA_7") (pintype "output"))
      (node (ref "R1") (pin "1") (pinfunction "1_1") (pintype "passive"))
    )
    (net (code "39") (name "Net-(IC1-OUTB)") (class "Default")
      (node (ref "IC1") (pin "5") (pinfunction "OUTB_5") (pintype "output"))
      (node (ref "R2") (pin "1") (pinfunction "1_1") (pintype "passive"))
    )
    (net (code "40") (name "Net-(IC2-OUTA)") (class "Default")
      (node (ref "IC2") (pin "7") (pinfunction "OUTA_7") (pintype "output"))
      (node (ref "R3") (pin "1") (pinfunction "1_1") (pintype "passive"))
    )
    (net (code "41") (name "Net-(IC2-OUTB)") (class "Default")
      (node (ref "IC2") (pin "5") (pinfunction "OUTB_5") (pintype "output"))
      (node (ref "R4") (pin "1") (pinfunction "1_1") (pintype "passive"))
    )
    (net (code "42") (name "Net-(IC3-OUTA)") (class "Default")
      (node (ref "IC3") (pin "7") (pinfunction "OUTA_7") (pintype "output"))
      (node (ref "R5") (pin "1") (pinfunction "1_1") (pintype "passive"))
    )
    (net (code "43") (name "Net-(IC3-OUTB)") (class "Default")
      (node (ref "IC3") (pin "5") (pinfunction "OUTB_5") (pintype "output"))
      (node (ref "R6") (pin "1") (pinfunction "1_1") (pintype "passive"))
    )
    (net (code "44") (name "Net-(IC4-OUTA)") (class "Default")
      (node (ref "IC4") (pin "7") (pinfunction "OUTA_7") (pintype "output"))
      (node (ref "R7") (pin "1") (pinfunction "1_1") (pintype "passive"))
    )
    (net (code "45") (name "Net-(IC4-OUTB)") (class "Default")
      (node (ref "IC4") (pin "5") (pinfunction "OUTB_5") (pintype "output"))
      (node (ref "R8") (pin "1") (pinfunction "1_1") (pintype "passive"))
    )
    (net (code "46") (name "Net-(IC5-OUTA)") (class "Default")
      (node (ref "IC5") (pin "7") (pinfunction "OUTA_7") (pintype "output"))
      (node (ref "R14") (pin "1") (pinfunction "1_1") (pintype "passive"))
    )
    (net (code "47") (name "Net-(IC5-OUTB)") (class "Default")
      (node (ref "IC5") (pin "5") (pinfunction "OUTB_5") (pintype "output"))
      (node (ref "R15") (pin "1") (pinfunction "1_1") (pintype "passive"))
    )
    (net (code "48") (name "Net-(IC6-OUTA)") (class "Default")
      (node (ref "IC6") (pin "7") (pinfunction "OUTA_7") (pintype "output"))
      (node (ref "R16") (pin "1") (pinfunction "1_1") (pintype "passive"))
    )
    (net (code "49") (name "Net-(IC6-OUTB)") (class "Default")
      (node (ref "IC6") (pin "5") (pinfunction "OUTB_5") (pintype "output"))
      (node (ref "R17") (pin "1") (pinfunction "1_1") (pintype "passive"))
    )
    (net (code "50") (name "Net-(IC7-OUTA)") (class "Default")
      (node (ref "IC7") (pin "7") (pinfunction "OUTA_7") (pintype "output"))
      (node (ref "R9") (pin "1") (pinfunction "1_1") (pintype "passive"))
    )
    (net (code "51") (name "Net-(IC7-OUTB)") (class "Default")
      (node (ref "IC7") (pin "5") (pinfunction "OUTB_5") (pintype "output"))
      (node (ref "R10") (pin "1") (pinfunction "1_1") (pintype "passive"))
    )
    (net (code "52") (name "Net-(IC8-OUTA)") (class "Default")
      (node (ref "IC8") (pin "7") (pinfunction "OUTA_7") (pintype "output"))
      (node (ref "R11") (pin "1") (pinfunction "1_1") (pintype "passive"))
    )
    (net (code "53") (name "Net-(IC8-OUTB)") (class "Default")
      (node (ref "IC8") (pin "5") (pinfunction "OUTB_5") (pintype "output"))
      (node (ref "R12") (pin "1") (pinfunction "1_1") (pintype "passive"))
    )
    (net (code "54") (name "Net-(IC9-O1)") (class "Default")
      (node (ref "IC9") (pin "18") (pinfunction "O1_18") (pintype "open_collector"))
      (node (ref "J4") (pin "3") (pinfunction "3_3") (pintype "bidirectional"))
    )
    (net (code "55") (name "Net-(IC9-O2)") (class "Default")
      (node (ref "IC9") (pin "17") (pinfunction "O2_17") (pintype "open_collector"))
      (node (ref "J4") (pin "4") (pinfunction "4_4") (pintype "bidirectional"))
    )
    (net (code "56") (name "Net-(IC9-O3)") (class "Default")
      (node (ref "IC9") (pin "16") (pinfunction "O3_16") (pintype "open_collector"))
      (node (ref "J4") (pin "5") (pinfunction "5_5") (pintype "bidirectional"))
    )
    (net (code "57") (name "Net-(IC9-O4)") (class "Default")
      (node (ref "IC9") (pin "15") (pinfunction "O4_15") (pintype "open_collector"))
      (node (ref "J4") (pin "6") (pinfunction "6_6") (pintype "bidirectional"))
    )
    (net (code "58") (name "Net-(IC9-O5)") (class "Default")
      (node (ref "IC9") (pin "14") (pinfunction "O5_14") (pintype "open_collector"))
      (node (ref "J4") (pin "7") (pinfunction "7_7") (pintype "bidirectional"))
    )
    (net (code "59") (name "Net-(IC9-O6)") (class "Default")
      (node (ref "IC9") (pin "13") (pinfunction "O6_13") (pintype "open_collector"))
      (node (ref "J4") (pin "8") (pinfunction "8_8") (pintype "bidirectional"))
    )
    (net (code "60") (name "Net-(IC9-O7)") (class "Default")
      (node (ref "IC9") (pin "12") (pinfunction "O7_12") (pintype "open_collector"))
      (node (ref "J4") (pin "9") (pinfunction "9_9") (pintype "bidirectional"))
    )
    (net (code "61") (name "Net-(IC9-O8)") (class "Default")
      (node (ref "IC9") (pin "11") (pinfunction "O8_11") (pintype "open_collector"))
      (node (ref "J4") (pin "10") (pinfunction "10_10") (pintype "bidirectional"))
    )
    (net (code "62") (name "Net-(IC10-O1)") (class "Default")
      (node (ref "IC10") (pin "18") (pinfunction "O1_18") (pintype "open_collector"))
      (node (ref "J5") (pin "2") (pinfunction "2_2") (pintype "bidirectional"))
    )
    (net (code "63") (name "Net-(IC10-O2)") (class "Default")
      (node (ref "IC10") (pin "17") (pinfunction "O2_17") (pintype "open_collector"))
      (node (ref "J5") (pin "3") (pinfunction "3_3") (pintype "bidirectional"))
    )
    (net (code "64") (name "Net-(IC10-O3)") (class "Default")
      (node (ref "IC10") (pin "16") (pinfunction "O3_16") (pintype "open_collector"))
      (node (ref "J5") (pin "4") (pinfunction "4_4") (pintype "bidirectional"))
    )
    (net (code "65") (name "Net-(IC10-O4)") (class "Default")
      (node (ref "IC10") (pin "15") (pinfunction "O4_15") (pintype "open_collector"))
      (node (ref "J5") (pin "5") (pinfunction "5_5") (pintype "bidirectional"))
    )
    (net (code "66") (name "Net-(IC10-O5)") (class "Default")
      (node (ref "IC10") (pin "14") (pinfunction "O5_14") (pintype "open_collector"))
      (node (ref "J5") (pin "6") (pinfunction "6_6") (pintype "bidirectional"))
    )
    (net (code "67") (name "Net-(IC10-O6)") (class "Default")
      (node (ref "IC10") (pin "13") (pinfunction "O6_13") (pintype "open_collector"))
      (node (ref "J5") (pin "8") (pinfunction "8_8") (pintype "bidirectional"))
    )
    (net (code "68") (name "Net-(IC10-O7)") (class "Default")
      (node (ref "IC10") (pin "12") (pinfunction "O7_12") (pintype "open_collector"))
      (node (ref "J5") (pin "9") (pinfunction "9_9") (pintype "bidirectional"))
    )
    (net (code "69") (name "Net-(IC10-O8)") (class "Default")
      (node (ref "IC10") (pin "11") (pinfunction "O8_11") (pintype "open_collector"))
      (node (ref "J5") (pin "10") (pinfunction "10_10") (pintype "bidirectional"))
    )
    (net (code "70") (name "Net-(IC11-O1)") (class "Default")
      (node (ref "IC11") (pin "18") (pinfunction "O1_18") (pintype "open_collector"))
      (node (ref "J6") (pin "2") (pinfunction "2_2") (pintype "bidirectional"))
    )
    (net (code "71") (name "Net-(IC11-O2)") (class "Default")
      (node (ref "IC11") (pin "17") (pinfunction "O2_17") (pintype "open_collector"))
      (node (ref "J6") (pin "3") (pinfunction "3_3") (pintype "bidirectional"))
    )
    (net (code "72") (name "Net-(IC11-O3)") (class "Default")
      (node (ref "IC11") (pin "16") (pinfunction "O3_16") (pintype "open_collector"))
      (node (ref "J6") (pin "4") (pinfunction "4_4") (pintype "bidirectional"))
    )
    (net (code "73") (name "Net-(IC11-O4)") (class "Default")
      (node (ref "IC11") (pin "15") (pinfunction "O4_15") (pintype "open_collector"))
      (node (ref "J6") (pin "5") (pinfunction "5_5") (pintype "bidirectional"))
    )
    (net (code "74") (name "Net-(IC11-O5)") (class "Default")
      (node (ref "IC11") (pin "14") (pinfunction "O5_14") (pintype "open_collector"))
      (node (ref "J6") (pin "6") (pinfunction "6_6") (pintype "bidirectional"))
    )
    (net (code "75") (name "Net-(IC11-O6)") (class "Default")
      (node (ref "IC11") (pin "13") (pinfunction "O6_13") (pintype "open_collector"))
      (node (ref "J6") (pin "7") (pinfunction "7_7") (pintype "bidirectional"))
    )
    (net (code "76") (name "Net-(IC11-O7)") (class "Default")
      (node (ref "IC11") (pin "12") (pinfunction "O7_12") (pintype "open_collector"))
      (node (ref "J6") (pin "9") (pinfunction "9_9") (pintype "bidirectional"))
    )
    (net (code "77") (name "Net-(IC11-O8)") (class "Default")
      (node (ref "IC11") (pin "11") (pinfunction "O8_11") (pintype "open_collector"))
      (node (ref "J6") (pin "10") (pinfunction "10_10") (pintype "bidirectional"))
    )
    (net (code "78") (name "Net-(IC12-O1)") (class "Default")
      (node (ref "IC12") (pin "18") (pinfunction "O1_18") (pintype "open_collector"))
      (node (ref "J7") (pin "2") (pinfunction "2_2") (pintype "bidirectional"))
    )
    (net (code "79") (name "Net-(IC12-O2)") (class "Default")
      (node (ref "IC12") (pin "17") (pinfunction "O2_17") (pintype "open_collector"))
      (node (ref "J7") (pin "3") (pinfunction "3_3") (pintype "bidirectional"))
    )
    (net (code "80") (name "Net-(IC12-O3)") (class "Default")
      (node (ref "IC12") (pin "16") (pinfunction "O3_16") (pintype "open_collector"))
      (node (ref "J7") (pin "4") (pinfunction "4_4") (pintype "bidirectional"))
    )
    (net (code "81") (name "Net-(IC12-O4)") (class "Default")
      (node (ref "IC12") (pin "15") (pinfunction "O4_15") (pintype "open_collector"))
      (node (ref "J7") (pin "5") (pinfunction "5_5") (pintype "bidirectional"))
    )
    (net (code "82") (name "Net-(IC12-O5)") (class "Default")
      (node (ref "IC12") (pin "14") (pinfunction "O5_14") (pintype "open_collector"))
      (node (ref "J7") (pin "6") (pinfunction "6_6") (pintype "bidirectional"))
    )
    (net (code "83") (name "Net-(IC12-O6)") (class "Default")
      (node (ref "IC12") (pin "13") (pinfunction "O6_13") (pintype "open_collector"))
      (node (ref "J7") (pin "7") (pinfunction "7_7") (pintype "bidirectional"))
    )
    (net (code "84") (name "Net-(IC12-O7)") (class "Default")
      (node (ref "IC12") (pin "12") (pinfunction "O7_12") (pintype "open_collector"))
      (node (ref "J7") (pin "8") (pinfunction "8_8") (pintype "bidirectional"))
    )
    (net (code "85") (name "Net-(IC12-O8)") (class "Default")
      (node (ref "IC12") (pin "11") (pinfunction "O8_11") (pintype "open_collector"))
      (node (ref "J7") (pin "10") (pinfunction "10_10") (pintype "bidirectional"))
    )
    (net (code "86") (name "Net-(IC13-VBAT)") (class "Default")
      (node (ref "BATT1") (pin "+") (pinfunction "+_+") (pintype "bidirectional"))
      (node (ref "IC13") (pin "3") (pinfunction "VBAT_3") (pintype "bidirectional"))
    )
    (net (code "87") (name "Net-(IC13-X1)") (class "Default")
      (node (ref "IC13") (pin "1") (pinfunction "X1_1") (pintype "bidirectional"))
      (node (ref "Y1") (pin "1") (pinfunction "CRYSTAL_1_1") (pintype "bidirectional"))
    )
    (net (code "88") (name "Net-(IC13-X2)") (class "Default")
      (node (ref "IC13") (pin "2") (pinfunction "X2_2") (pintype "bidirectional"))
      (node (ref "Y1") (pin "2") (pinfunction "CRYSTAL_2_2") (pintype "bidirectional"))
    )
    (net (code "89") (name "Net-(PICO1-Pad3V3)") (class "Default")
      (node (ref "PICO1") (pin "3V3") (pinfunction "3V3_3V3") (pintype "bidirectional"))
      (node (ref "R18") (pin "2") (pinfunction "2_2") (pintype "passive"))
    )
    (net (code "90") (name "Net-(PICO2-Pad3V3)") (class "Default")
      (node (ref "PICO2") (pin "3V3") (pinfunction "3V3_3V3") (pintype "bidirectional"))
      (node (ref "R32") (pin "2") (pinfunction "2_2") (pintype "passive"))
    )
    (net (code "91") (name "Net-(Q1-G)") (class "Default")
      (node (ref "Q1") (pin "1") (pinfunction "G_1") (pintype "passive"))
      (node (ref "R1") (pin "2") (pinfunction "2_2") (pintype "passive"))
    )
    (net (code "92") (name "Net-(Q2-G)") (class "Default")
      (node (ref "Q2") (pin "1") (pinfunction "G_1") (pintype "passive"))
      (node (ref "R2") (pin "2") (pinfunction "2_2") (pintype "passive"))
    )
    (net (code "93") (name "Net-(Q3-G)") (class "Default")
      (node (ref "Q3") (pin "1") (pinfunction "G_1") (pintype "passive"))
      (node (ref "R3") (pin "2") (pinfunction "2_2") (pintype "passive"))
    )
    (net (code "94") (name "Net-(Q4-G)") (class "Default")
      (node (ref "Q4") (pin "1") (pinfunction "G_1") (pintype "passive"))
      (node (ref "R4") (pin "2") (pinfunction "2_2") (pintype "passive"))
    )
    (net (code "95") (name "Net-(Q5-G)") (class "Default")
      (node (ref "Q5") (pin "1") (pinfunction "G_1") (pintype "passive"))
      (node (ref "R5") (pin "2") (pinfunction "2_2") (pintype "passive"))
    )
    (net (code "96") (name "Net-(Q6-G)") (class "Default")
      (node (ref "Q6") (pin "1") (pinfunction "G_1") (pintype "passive"))
      (node (ref "R6") (pin "2") (pinfunction "2_2") (pintype "passive"))
    )
    (net (code "97") (name "Net-(Q7-G)") (class "Default")
      (node (ref "Q7") (pin "1") (pinfunction "G_1") (pintype "passive"))
      (node (ref "R7") (pin "2") (pinfunction "2_2") (pintype "passive"))
    )
    (net (code "98") (name "Net-(Q8-G)") (class "Default")
      (node (ref "Q8") (pin "1") (pinfunction "G_1") (pintype "passive"))
      (node (ref "R8") (pin "2") (pinfunction "2_2") (pintype "passive"))
    )
    (net (code "99") (name "Net-(Q9-G)") (class "Default")
      (node (ref "Q9") (pin "1") (pinfunction "G_1") (pintype "passive"))
      (node (ref "R14") (pin "2") (pinfunction "2_2") (pintype "passive"))
    )
    (net (code "100") (name "Net-(Q10-G)") (class "Default")
      (node (ref "Q10") (pin "1") (pinfunction "G_1") (pintype "passive"))
      (node (ref "R15") (pin "2") (pinfunction "2_2") (pintype "passive"))
    )
    (net (code "101") (name "Net-(Q11-G)") (class "Default")
      (node (ref "Q11") (pin "1") (pinfunction "G_1") (pintype "passive"))
      (node (ref "R16") (pin "2") (pinfunction "2_2") (pintype "passive"))
    )
    (net (code "102") (name "Net-(Q12-G)") (class "Default")
      (node (ref "Q12") (pin "1") (pinfunction "G_1") (pintype "passive"))
      (node (ref "R17") (pin "2") (pinfunction "2_2") (pintype "passive"))
    )
    (net (code "103") (name "Net-(Q13-G)") (class "Default")
      (node (ref "Q13") (pin "1") (pinfunction "G_1") (pintype "passive"))
      (node (ref "R9") (pin "2") (pinfunction "2_2") (pintype "passive"))
    )
    (net (code "104") (name "Net-(Q14-G)") (class "Default")
      (node (ref "Q14") (pin "1") (pinfunction "G_1") (pintype "passive"))
      (node (ref "R10") (pin "2") (pinfunction "2_2") (pintype "passive"))
    )
    (net (code "105") (name "Net-(Q15-G)") (class "Default")
      (node (ref "Q15") (pin "1") (pinfunction "G_1") (pintype "passive"))
      (node (ref "R11") (pin "2") (pinfunction "2_2") (pintype "passive"))
    )
    (net (code "106") (name "Net-(Q16-G)") (class "Default")
      (node (ref "Q16") (pin "1") (pinfunction "G_1") (pintype "passive"))
      (node (ref "R12") (pin "2") (pinfunction "2_2") (pintype "passive"))
    )
    (net (code "107") (name "Net-(Q17-B)") (class "Default")
      (node (ref "Q17") (pin "2") (pinfunction "B_2") (pintype "bidirectional"))
      (node (ref "R33") (pin "2") (pinfunction "2_2") (pintype "passive"))
    )
    (net (code "108") (name "Net-(Q17-C)") (class "Default")
      (node (ref "PICO2") (pin "RUN") (pinfunction "RUN_RUN") (pintype "bidirectional"))
      (node (ref "Q17") (pin "3") (pinfunction "C_3") (pintype "bidirectional"))
      (node (ref "R32") (pin "1") (pinfunction "1_1") (pintype "passive"))
      (node (ref "S2") (pin "3") (pinfunction "P_3") (pintype "passive"))
      (node (ref "S2") (pin "4") (pinfunction "P1_4") (pintype "passive"))
    )
    (net (code "109") (name "Net-(Q18-B)") (class "Default")
      (node (ref "Q18") (pin "2") (pinfunction "B_2") (pintype "bidirectional"))
      (node (ref "R13") (pin "2") (pinfunction "2_2") (pintype "passive"))
    )
    (net (code "110") (name "Net-(Q18-C)") (class "Default")
      (node (ref "PICO1") (pin "RUN") (pinfunction "RUN_RUN") (pintype "bidirectional"))
      (node (ref "Q18") (pin "3") (pinfunction "C_3") (pintype "bidirectional"))
      (node (ref "R18") (pin "1") (pinfunction "1_1") (pintype "passive"))
      (node (ref "S1") (pin "3") (pinfunction "P_3") (pintype "passive"))
      (node (ref "S1") (pin "4") (pinfunction "P1_4") (pintype "passive"))
    )
    (net (code "111") (name "OUT13") (class "Default")
      (node (ref "J1") (pin "1") (pinfunction "1_1") (pintype "bidirectional"))
      (node (ref "Q1") (pin "2") (pinfunction "D_2") (pintype "passive"))
    )
    (net (code "112") (name "OUT14") (class "Default")
      (node (ref "J1") (pin "2") (pinfunction "2_2") (pintype "bidirectional"))
      (node (ref "Q2") (pin "2") (pinfunction "D_2") (pintype "passive"))
    )
    (net (code "113") (name "OUT15") (class "Default")
      (node (ref "J1") (pin "4") (pinfunction "4_4") (pintype "bidirectional"))
      (node (ref "Q3") (pin "2") (pinfunction "D_2") (pintype "passive"))
    )
    (net (code "114") (name "OUT16") (class "Default")
      (node (ref "J1") (pin "5") (pinfunction "5_5") (pintype "bidirectional"))
      (node (ref "Q4") (pin "2") (pinfunction "D_2") (pintype "passive"))
    )
    (net (code "115") (name "OUT17") (class "Default")
      (node (ref "J1") (pin "6") (pinfunction "6_6") (pintype "bidirectional"))
      (node (ref "Q5") (pin "2") (pinfunction "D_2") (pintype "passive"))
    )
    (net (code "116") (name "OUT18") (class "Default")
      (node (ref "J1") (pin "7") (pinfunction "7_7") (pintype "bidirectional"))
      (node (ref "Q6") (pin "2") (pinfunction "D_2") (pintype "passive"))
    )
    (net (code "117") (name "OUT19") (class "Default")
      (node (ref "J1") (pin "8") (pinfunction "8_8") (pintype "bidirectional"))
      (node (ref "Q7") (pin "2") (pinfunction "D_2") (pintype "passive"))
    )
    (net (code "118") (name "OUT20") (class "Default")
      (node (ref "J1") (pin "9") (pinfunction "9_9") (pintype "bidirectional"))
      (node (ref "Q8") (pin "2") (pinfunction "D_2") (pintype "passive"))
    )
    (net (code "119") (name "OUT21") (class "Default")
      (node (ref "J2") (pin "1") (pinfunction "1_1") (pintype "bidirectional"))
      (node (ref "Q9") (pin "2") (pinfunction "D_2") (pintype "passive"))
    )
    (net (code "120") (name "OUT22") (class "Default")
      (node (ref "J2") (pin "2") (pinfunction "2_2") (pintype "bidirectional"))
      (node (ref "Q10") (pin "2") (pinfunction "D_2") (pintype "passive"))
    )
    (net (code "121") (name "OUT23") (class "Default")
      (node (ref "J2") (pin "3") (pinfunction "3_3") (pintype "bidirectional"))
      (node (ref "Q11") (pin "2") (pinfunction "D_2") (pintype "passive"))
    )
    (net (code "122") (name "OUT24") (class "Default")
      (node (ref "J2") (pin "5") (pinfunction "5_5") (pintype "bidirectional"))
      (node (ref "Q12") (pin "2") (pinfunction "D_2") (pintype "passive"))
    )
    (net (code "123") (name "OUT25") (class "Default")
      (node (ref "J2") (pin "6") (pinfunction "6_6") (pintype "bidirectional"))
      (node (ref "Q13") (pin "2") (pinfunction "D_2") (pintype "passive"))
    )
    (net (code "124") (name "OUT26") (class "Default")
      (node (ref "J2") (pin "7") (pinfunction "7_7") (pintype "bidirectional"))
      (node (ref "Q14") (pin "2") (pinfunction "D_2") (pintype "passive"))
    )
    (net (code "125") (name "OUT27") (class "Default")
      (node (ref "J2") (pin "8") (pinfunction "8_8") (pintype "bidirectional"))
      (node (ref "Q15") (pin "2") (pinfunction "D_2") (pintype "passive"))
    )
    (net (code "126") (name "OUT28") (class "Default")
      (node (ref "J2") (pin "9") (pinfunction "9_9") (pintype "bidirectional"))
      (node (ref "Q16") (pin "2") (pinfunction "D_2") (pintype "passive"))
    )
    (net (code "127") (name "OUTCTL13") (class "Default")
      (node (ref "IC1") (pin "2") (pinfunction "INA_2") (pintype "input"))
      (node (ref "PICO1") (pin "GP28_A2") (pinfunction "GP28_A2_GP28_A2") (pintype "bidirectional"))
    )
    (net (code "128") (name "OUTCTL14") (class "Default")
      (node (ref "IC1") (pin "4") (pinfunction "INB_4") (pintype "input"))
      (node (ref "PICO1") (pin "GP0") (pinfunction "GP0_GP0") (pintype "bidirectional"))
    )
    (net (code "129") (name "OUTCTL15") (class "Default")
      (node (ref "IC2") (pin "2") (pinfunction "INA_2") (pintype "input"))
      (node (ref "PICO1") (pin "GP1") (pinfunction "GP1_GP1") (pintype "bidirectional"))
    )
    (net (code "130") (name "OUTCTL16") (class "Default")
      (node (ref "IC2") (pin "4") (pinfunction "INB_4") (pintype "input"))
      (node (ref "PICO1") (pin "GP22") (pinfunction "GP22_GP22") (pintype "bidirectional"))
    )
    (net (code "131") (name "OUTCTL17") (class "Default")
      (node (ref "IC3") (pin "2") (pinfunction "INA_2") (pintype "input"))
      (node (ref "PICO1") (pin "GP21") (pinfunction "GP21_GP21") (pintype "bidirectional"))
    )
    (net (code "132") (name "OUTCTL18") (class "Default")
      (node (ref "IC3") (pin "4") (pinfunction "INB_4") (pintype "input"))
      (node (ref "PICO1") (pin "GP20") (pinfunction "GP20_GP20") (pintype "bidirectional"))
    )
    (net (code "133") (name "OUTCTL19") (class "Default")
      (node (ref "IC4") (pin "2") (pinfunction "INA_2") (pintype "input"))
      (node (ref "PICO1") (pin "GP19") (pinfunction "GP19_GP19") (pintype "bidirectional"))
    )
    (net (code "134") (name "OUTCTL20") (class "Default")
      (node (ref "IC4") (pin "4") (pinfunction "INB_4") (pintype "input"))
      (node (ref "PICO1") (pin "GP18") (pinfunction "GP18_GP18") (pintype "bidirectional"))
    )
    (net (code "135") (name "OUTCTL21") (class "Default")
      (node (ref "IC5") (pin "2") (pinfunction "INA_2") (pintype "input"))
      (node (ref "PICO1") (pin "GP17") (pinfunction "GP17_GP17") (pintype "bidirectional"))
    )
    (net (code "136") (name "OUTCTL22") (class "Default")
      (node (ref "IC5") (pin "4") (pinfunction "INB_4") (pintype "input"))
      (node (ref "PICO1") (pin "GP16") (pinfunction "GP16_GP16") (pintype "bidirectional"))
    )
    (net (code "137") (name "OUTCTL23") (class "Default")
      (node (ref "IC6") (pin "2") (pinfunction "INA_2") (pintype "input"))
      (node (ref "PICO1") (pin "GP15") (pinfunction "GP15_GP15") (pintype "bidirectional"))
    )
    (net (code "138") (name "OUTCTL24") (class "Default")
      (node (ref "IC6") (pin "4") (pinfunction "INB_4") (pintype "input"))
      (node (ref "PICO1") (pin "GP14") (pinfunction "GP14_GP14") (pintype "bidirectional"))
    )
    (net (code "139") (name "OUTCTL25") (class "Default")
      (node (ref "IC7") (pin "2") (pinfunction "INA_2") (pintype "input"))
      (node (ref "PICO1") (pin "GP13") (pinfunction "GP13_GP13") (pintype "bidirectional"))
    )
    (net (code "140") (name "OUTCTL26") (class "Default")
      (node (ref "IC7") (pin "4") (pinfunction "INB_4") (pintype "input"))
      (node (ref "PICO1") (pin "GP12") (pinfunction "GP12_GP12") (pintype "bidirectional"))
    )
    (net (code "141") (name "OUTCTL27") (class "Default")
      (node (ref "IC8") (pin "2") (pinfunction "INA_2") (pintype "input"))
      (node (ref "PICO1") (pin "GP11") (pinfunction "GP11_GP11") (pintype "bidirectional"))
    )
    (net (code "142") (name "OUTCTL28") (class "Default")
      (node (ref "IC8") (pin "4") (pinfunction "INB_4") (pintype "input"))
      (node (ref "PICO1") (pin "GP10") (pinfunction "GP10_GP10") (pintype "bidirectional"))
    )
    (net (code "143") (name "SCL") (class "Default")
      (node (ref "IC13") (pin "6") (pinfunction "SCL_6") (pintype "bidirectional"))
      (node (ref "J8") (pin "3") (pinfunction "3_3") (pintype "passive"))
      (node (ref "PICO1") (pin "GP27_A1") (pinfunction "GP27_A1_GP27_A1") (pintype "bidirectional"))
      (node (ref "PICO2") (pin "GP27_A1") (pinfunction "GP27_A1_GP27_A1") (pintype "bidirectional"))
    )
    (net (code "144") (name "SDA") (class "Default")
      (node (ref "IC13") (pin "5") (pinfunction "SDA_5") (pintype "bidirectional"))
      (node (ref "J8") (pin "5") (pinfunction "5_5") (pintype "passive"))
      (node (ref "PICO1") (pin "GP26_A0") (pinfunction "GP26_A0_GP26_A0") (pintype "bidirectional"))
      (node (ref "PICO2") (pin "GP26_A0") (pinfunction "GP26_A0_GP26_A0") (pintype "bidirectional"))
    )
    (net (code "145") (name "VBUS") (class "Default")
      (node (ref "D1") (pin "2") (pinfunction "A_2") (pintype "bidirectional"))
      (node (ref "D2") (pin "2") (pinfunction "A_2") (pintype "bidirectional"))
      (node (ref "IC13") (pin "8") (pinfunction "VCC_8") (pintype "bidirectional"))
      (node (ref "J8") (pin "1") (pinfunction "1_1") (pintype "passive"))
    )
    (net (code "146") (name "unconnected-(IC9-CD+-Pad10)") (class "Default")
      (node (ref "IC9") (pin "10") (pinfunction "CD+_10") (pintype "passive"))
    )
    (net (code "147") (name "unconnected-(IC10-CD+-Pad10)") (class "Default")
      (node (ref "IC10") (pin "10") (pinfunction "CD+_10") (pintype "passive"))
    )
    (net (code "148") (name "unconnected-(IC11-CD+-Pad10)") (class "Default")
      (node (ref "IC11") (pin "10") (pinfunction "CD+_10") (pintype "passive"))
    )
    (net (code "149") (name "unconnected-(IC12-CD+-Pad10)") (class "Default")
      (node (ref "IC12") (pin "10") (pinfunction "CD+_10") (pintype "passive"))
    )
    (net (code "150") (name "unconnected-(IC13-SQW{slash}OUT-Pad7)") (class "Default")
      (node (ref "IC13") (pin "7") (pinfunction "SQW/OUT_7") (pintype "bidirectional"))
    )
    (net (code "151") (name "unconnected-(J1-Pad3)") (class "Default")
      (node (ref "J1") (pin "3") (pinfunction "3_3") (pintype "bidirectional"))
    )
    (net (code "152") (name "unconnected-(J2-Pad4)") (class "Default")
      (node (ref "J2") (pin "4") (pinfunction "4_4") (pintype "bidirectional"))
    )
    (net (code "153") (name "unconnected-(J4-Pad2)") (class "Default")
      (node (ref "J4") (pin "2") (pinfunction "2_2") (pintype "bidirectional"))
    )
    (net (code "154") (name "unconnected-(J5-Pad7)") (class "Default")
      (node (ref "J5") (pin "7") (pinfunction "7_7") (pintype "bidirectional"))
    )
    (net (code "155") (name "unconnected-(J6-Pad8)") (class "Default")
      (node (ref "J6") (pin "8") (pinfunction "8_8") (pintype "bidirectional"))
    )
    (net (code "156") (name "unconnected-(J7-Pad9)") (class "Default")
      (node (ref "J7") (pin "9") (pinfunction "9_9") (pintype "bidirectional"))
    )
    (net (code "157") (name "unconnected-(PICO1-Pad3V3_EN)") (class "Default")
      (node (ref "PICO1") (pin "3V3_EN") (pinfunction "3V3_EN_3V3_EN") (pintype "bidirectional"))
    )
    (net (code "158") (name "unconnected-(PICO1-PadADC_VREF)") (class "Default")
      (node (ref "PICO1") (pin "ADC_VREF") (pinfunction "ADC_VREF_ADC_VREF") (pintype "bidirectional"))
    )
    (net (code "159") (name "unconnected-(PICO1-PadVBUS)") (class "Default")
      (node (ref "PICO1") (pin "VBUS") (pinfunction "VBUS_VBUS") (pintype "bidirectional"))
    )
    (net (code "160") (name "unconnected-(PICO2-Pad3V3_EN)") (class "Default")
      (node (ref "PICO2") (pin "3V3_EN") (pinfunction "3V3_EN_3V3_EN") (pintype "bidirectional"))
    )
    (net (code "161") (name "unconnected-(PICO2-PadADC_VREF)") (class "Default")
      (node (ref "PICO2") (pin "ADC_VREF") (pinfunction "ADC_VREF_ADC_VREF") (pintype "bidirectional"))
    )
    (net (code "162") (name "unconnected-(PICO2-PadVBUS)") (class "Default")
      (node (ref "PICO2") (pin "VBUS") (pinfunction "VBUS_VBUS") (pintype "bidirectional"))
    )
    (net (code "163") (name "{slash}PERIPHERAL_POWER_ENABLE") (class "Default")
      (node (ref "J8") (pin "7") (pinfunction "7_7") (pintype "passive"))
      (node (ref "R13") (pin "1") (pinfunction "1_1") (pintype "passive"))
      (node (ref "R33") (pin "1") (pinfunction "1_1") (pintype "passive"))
    )
  )
)
